# Sheet1.net
KiCad netlist of a schematic drawn in Altium Designer
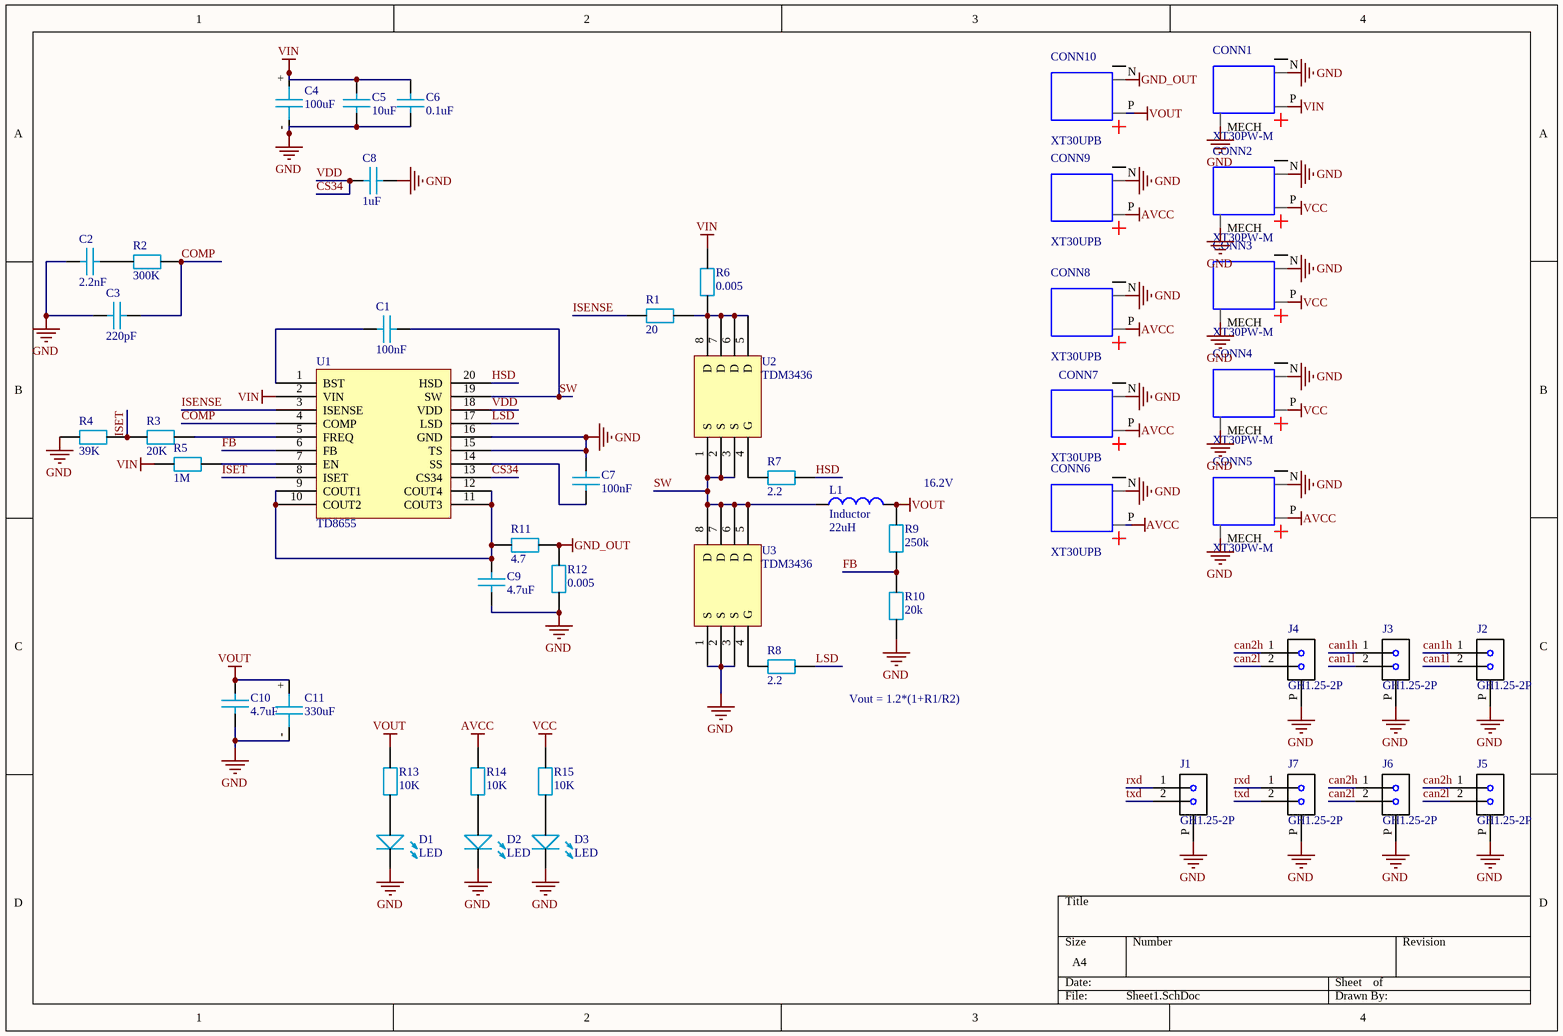
[diagram p0: Sheet1.SchDoc]

(export (version "E")
  (design (tool "Eeschema 10.0.6"))
  (components
    (comp (ref "C1") (value "100nF") (footprint "0603_C") (libsource (lib "elin私人订制") (part "C")))
    (comp (ref "C2") (value "2.2nF") (footprint "0603_C") (libsource (lib "elin私人订制") (part "C")))
    (comp (ref "C3") (value "220pF") (footprint "0603_C") (libsource (lib "elin私人订制") (part "C")))
    (comp (ref "C4") (value "100uF") (footprint "rad8*11") (libsource (lib "elin私人订制") (part "CD")))
    (comp (ref "C5") (value "10uF") (footprint "0805_C") (libsource (lib "elin私人订制") (part "C")))
    (comp (ref "C6") (value "0.1uF") (footprint "0805_C") (libsource (lib "elin私人订制") (part "C")))
    (comp (ref "C7") (value "100nF") (footprint "0603_C") (libsource (lib "elin私人订制") (part "C")))
    (comp (ref "C8") (value "1uF") (footprint "0603_C") (libsource (lib "elin私人订制") (part "C")))
    (comp (ref "C9") (value "4.7uF") (footprint "0603_C") (libsource (lib "elin私人订制") (part "C")))
    (comp (ref "C10") (value "4.7uF") (footprint "0805_C") (libsource (lib "elin私人订制") (part "C")))
    (comp (ref "C11") (value "330uF") (footprint "dip-ec10*17") (libsource (lib "elin私人订制") (part "CD")))
    (comp (ref "CONN1")
      (value "XT30PW-M")
      (footprint "xt30pw-m")
      (description "卧式焊板XT30（公）")
      (libsource (lib "RM私人定制") (part "XT30PW-M"))
    )
    (comp (ref "CONN2")
      (value "XT30PW-M")
      (footprint "xt30pw-m")
      (description "卧式焊板XT30（公）")
      (libsource (lib "RM私人定制") (part "XT30PW-M"))
    )
    (comp (ref "CONN3")
      (value "XT30PW-M")
      (footprint "xt30pw-m")
      (description "卧式焊板XT30（公）")
      (libsource (lib "RM私人定制") (part "XT30PW-M"))
    )
    (comp (ref "CONN4")
      (value "XT30PW-M")
      (footprint "xt30pw-m")
      (description "卧式焊板XT30（公）")
      (libsource (lib "RM私人定制") (part "XT30PW-M"))
    )
    (comp (ref "CONN5")
      (value "XT30PW-M")
      (footprint "xt30pw-m")
      (description "卧式焊板XT30（公）")
      (libsource (lib "RM私人定制") (part "XT30PW-M"))
    )
    (comp (ref "CONN6")
      (value "XT30UPB")
      (footprint "XT30UPB")
      (description "立式焊板XT30（通用）")
      (libsource (lib "RM私人定制") (part "XT30UPB"))
    )
    (comp (ref "CONN7")
      (value "XT30UPB")
      (footprint "XT30UPB")
      (description "立式焊板XT30（通用）")
      (libsource (lib "RM私人定制") (part "XT30UPB"))
    )
    (comp (ref "CONN8")
      (value "XT30UPB")
      (footprint "XT30UPB")
      (description "立式焊板XT30（通用）")
      (libsource (lib "RM私人定制") (part "XT30UPB"))
    )
    (comp (ref "CONN9")
      (value "XT30UPB")
      (footprint "XT30UPB")
      (description "立式焊板XT30（通用）")
      (libsource (lib "RM私人定制") (part "XT30UPB"))
    )
    (comp (ref "CONN10")
      (value "XT30UPB")
      (footprint "XT30UPB")
      (description "立式焊板XT30（通用）")
      (libsource (lib "RM私人定制") (part "XT30UPB"))
    )
    (comp (ref "D1") (value "LED") (footprint "LED_0805") (libsource (lib "elin私人订制") (part "LED")))
    (comp (ref "D2") (value "LED") (footprint "LED_0805") (libsource (lib "elin私人订制") (part "LED")))
    (comp (ref "D3") (value "LED") (footprint "LED_0805") (libsource (lib "elin私人订制") (part "LED")))
    (comp (ref "J1")
      (value "GH1.25-2P")
      (footprint "gh1.25-2p-立")
      (fields (field (name "MP") "53261-0271") (field (name "MF") "Molex"))
      (libsource (lib "RM私人定制") (part "GH1.25-2P"))
    )
    (comp (ref "J2")
      (value "GH1.25-2P")
      (footprint "gh1.25-2p-立")
      (fields (field (name "MP") "53261-0271") (field (name "MF") "Molex"))
      (libsource (lib "RM私人定制") (part "GH1.25-2P"))
    )
    (comp (ref "J3")
      (value "GH1.25-2P")
      (footprint "gh1.25-2p-立")
      (fields (field (name "MP") "53261-0271") (field (name "MF") "Molex"))
      (libsource (lib "RM私人定制") (part "GH1.25-2P"))
    )
    (comp (ref "J4")
      (value "GH1.25-2P")
      (footprint "gh1.25-2p-立")
      (fields (field (name "MP") "53261-0271") (field (name "MF") "Molex"))
      (libsource (lib "RM私人定制") (part "GH1.25-2P"))
    )
    (comp (ref "J5")
      (value "GH1.25-2P")
      (footprint "gh1.25-2p-立")
      (fields (field (name "MP") "53261-0271") (field (name "MF") "Molex"))
      (libsource (lib "RM私人定制") (part "GH1.25-2P"))
    )
    (comp (ref "J6")
      (value "GH1.25-2P")
      (footprint "gh1.25-2p-立")
      (fields (field (name "MP") "53261-0271") (field (name "MF") "Molex"))
      (libsource (lib "RM私人定制") (part "GH1.25-2P"))
    )
    (comp (ref "J7")
      (value "GH1.25-2P")
      (footprint "gh1.25-2p-立")
      (fields (field (name "MP") "53261-0271") (field (name "MF") "Molex"))
      (libsource (lib "RM私人定制") (part "GH1.25-2P"))
    )
    (comp (ref "L1")
      (value "Inductor")
      (footprint "SRP1265A-220M")
      (fields (field (name "ALTIUM_VALUE") "22uH") (field (name "PUBLISHER") "Altium Limited"))
      (libsource (lib "Miscellaneous Devices") (part "Inductor"))
    )
    (comp (ref "R1") (value "20") (footprint "0603-R") (libsource (lib "elin私人订制") (part "R")))
    (comp (ref "R2") (value "300K") (footprint "0603-R") (libsource (lib "elin私人订制") (part "R")))
    (comp (ref "R3") (value "20K") (footprint "0603-R") (libsource (lib "elin私人订制") (part "R")))
    (comp (ref "R4") (value "39K") (footprint "0603-R") (libsource (lib "elin私人订制") (part "R")))
    (comp (ref "R5") (value "1M") (footprint "0603-R") (libsource (lib "elin私人订制") (part "R")))
    (comp (ref "R6") (value "0.005") (footprint "2512") (libsource (lib "elin私人订制") (part "R")))
    (comp (ref "R7") (value "2.2") (footprint "0603-R") (libsource (lib "elin私人订制") (part "R")))
    (comp (ref "R8") (value "2.2") (footprint "0603-R") (libsource (lib "elin私人订制") (part "R")))
    (comp (ref "R9") (value "250k") (footprint "0603-R") (libsource (lib "elin私人订制") (part "R")))
    (comp (ref "R10") (value "20k") (footprint "0603-R") (libsource (lib "elin私人订制") (part "R")))
    (comp (ref "R11") (value "4.7") (footprint "0603-R") (libsource (lib "elin私人订制") (part "R")))
    (comp (ref "R12") (value "0.005") (footprint "2512") (libsource (lib "elin私人订制") (part "R")))
    (comp (ref "R13") (value "10K") (footprint "0603-R") (libsource (lib "elin私人订制") (part "R")))
    (comp (ref "R14") (value "10K") (footprint "0603-R") (libsource (lib "elin私人订制") (part "R")))
    (comp (ref "R15") (value "10K") (footprint "0603-R") (libsource (lib "elin私人订制") (part "R")))
    (comp (ref "U1")
      (value "TD8655")
      (footprint "LC-QFN-20_4x4x05P")
      (libsource (lib "elin私人订制") (part "TD8655"))
    )
    (comp (ref "U2")
      (value "TDM3436")
      (footprint "LC-DFN-8_5x6mm")
      (libsource (lib "elin私人订制") (part "TDM3436"))
    )
    (comp (ref "U3")
      (value "TDM3436")
      (footprint "LC-DFN-8_5x6mm")
      (libsource (lib "elin私人订制") (part "TDM3436"))
    )
  )
  (nets
    (net (code "1") (name "/COMP") (class "Default")
      (node (ref "C3") (pin "2") (pinfunction "2_2") (pintype "passive"))
      (node (ref "R2") (pin "2") (pinfunction "2_2") (pintype "passive"))
      (node (ref "U1") (pin "4") (pinfunction "COMP_4") (pintype "passive"))
    )
    (net (code "2") (name "/CS34") (class "Default")
      (node (ref "C8") (pin "2") (pinfunction "2_2") (pintype "passive"))
      (node (ref "U1") (pin "13") (pinfunction "CS34_13") (pintype "passive"))
      (node (ref "U1") (pin "18") (pinfunction "VDD_18") (pintype "passive"))
    )
    (net (code "3") (name "/FB") (class "Default")
      (node (ref "R10") (pin "2") (pinfunction "2_2") (pintype "passive"))
      (node (ref "R9") (pin "1") (pinfunction "1_1") (pintype "passive"))
      (node (ref "U1") (pin "6") (pinfunction "FB_6") (pintype "passive"))
    )
    (net (code "4") (name "/HSD") (class "Default")
      (node (ref "R7") (pin "1") (pinfunction "1_1") (pintype "passive"))
      (node (ref "U1") (pin "20") (pinfunction "HSD_20") (pintype "passive"))
    )
    (net (code "5") (name "/ISENSE") (class "Default")
      (node (ref "R1") (pin "1") (pinfunction "1_1") (pintype "passive"))
      (node (ref "U1") (pin "3") (pinfunction "ISENSE_3") (pintype "passive"))
    )
    (net (code "6") (name "/ISET") (class "Default")
      (node (ref "R3") (pin "1") (pinfunction "1_1") (pintype "passive"))
      (node (ref "R4") (pin "2") (pinfunction "2_2") (pintype "passive"))
      (node (ref "U1") (pin "8") (pinfunction "ISET_8") (pintype "passive"))
    )
    (net (code "7") (name "/LSD") (class "Default")
      (node (ref "R8") (pin "1") (pinfunction "1_1") (pintype "passive"))
      (node (ref "U1") (pin "17") (pinfunction "LSD_17") (pintype "passive"))
    )
    (net (code "8") (name "/SW") (class "Default")
      (node (ref "C1") (pin "1") (pinfunction "1_1") (pintype "passive"))
      (node (ref "L1") (pin "1") (pinfunction "1_1") (pintype "passive"))
      (node (ref "U1") (pin "19") (pinfunction "SW_19") (pintype "passive"))
      (node (ref "U2") (pin "1") (pinfunction "S_1") (pintype "passive"))
      (node (ref "U2") (pin "2") (pinfunction "S_2") (pintype "passive"))
      (node (ref "U2") (pin "3") (pinfunction "S_3") (pintype "passive"))
      (node (ref "U3") (pin "5") (pinfunction "D_5") (pintype "passive"))
      (node (ref "U3") (pin "6") (pinfunction "D_6") (pintype "passive"))
      (node (ref "U3") (pin "7") (pinfunction "D_7") (pintype "passive"))
      (node (ref "U3") (pin "8") (pinfunction "D_8") (pintype "passive"))
    )
    (net (code "9") (name "/can1h") (class "Default")
      (node (ref "J2") (pin "1") (pinfunction "1_1") (pintype "passive"))
      (node (ref "J3") (pin "1") (pinfunction "1_1") (pintype "passive"))
    )
    (net (code "10") (name "/can1l") (class "Default")
      (node (ref "J2") (pin "2") (pinfunction "2_2") (pintype "passive"))
      (node (ref "J3") (pin "2") (pinfunction "2_2") (pintype "passive"))
    )
    (net (code "11") (name "/can2h") (class "Default")
      (node (ref "J4") (pin "1") (pinfunction "1_1") (pintype "passive"))
      (node (ref "J5") (pin "1") (pinfunction "1_1") (pintype "passive"))
      (node (ref "J6") (pin "1") (pinfunction "1_1") (pintype "passive"))
    )
    (net (code "12") (name "/can2l") (class "Default")
      (node (ref "J4") (pin "2") (pinfunction "2_2") (pintype "passive"))
      (node (ref "J5") (pin "2") (pinfunction "2_2") (pintype "passive"))
      (node (ref "J6") (pin "2") (pinfunction "2_2") (pintype "passive"))
    )
    (net (code "13") (name "/rxd") (class "Default")
      (node (ref "J1") (pin "1") (pinfunction "1_1") (pintype "passive"))
      (node (ref "J7") (pin "1") (pinfunction "1_1") (pintype "passive"))
    )
    (net (code "14") (name "/txd") (class "Default")
      (node (ref "J1") (pin "2") (pinfunction "2_2") (pintype "passive"))
      (node (ref "J7") (pin "2") (pinfunction "2_2") (pintype "passive"))
    )
    (net (code "15") (name "AVCC") (class "Default")
      (node (ref "CONN5") (pin "P") (pintype "passive"))
      (node (ref "CONN6") (pin "P") (pintype "passive"))
      (node (ref "CONN7") (pin "P") (pintype "passive"))
      (node (ref "CONN8") (pin "P") (pintype "passive"))
      (node (ref "CONN9") (pin "P") (pintype "passive"))
      (node (ref "R14") (pin "2") (pinfunction "2_2") (pintype "passive"))
    )
    (net (code "16") (name "GND") (class "Default")
      (node (ref "C10") (pin "1") (pinfunction "1_1") (pintype "passive"))
      (node (ref "C11") (pin "-") (pinfunction "2_-") (pintype "passive"))
      (node (ref "C2") (pin "1") (pinfunction "1_1") (pintype "passive"))
      (node (ref "C3") (pin "1") (pinfunction "1_1") (pintype "passive"))
      (node (ref "C4") (pin "-") (pinfunction "2_-") (pintype "passive"))
      (node (ref "C5") (pin "1") (pinfunction "1_1") (pintype "passive"))
      (node (ref "C6") (pin "1") (pinfunction "1_1") (pintype "passive"))
      (node (ref "C7") (pin "2") (pinfunction "2_2") (pintype "passive"))
      (node (ref "C8") (pin "1") (pinfunction "1_1") (pintype "passive"))
      (node (ref "C9") (pin "1") (pinfunction "1_1") (pintype "passive"))
      (node (ref "CONN1") (pin "3") (pinfunction "MECH_3") (pintype "passive"))
      (node (ref "CONN1") (pin "N") (pintype "passive"))
      (node (ref "CONN2") (pin "3") (pinfunction "MECH_3") (pintype "passive"))
      (node (ref "CONN2") (pin "N") (pintype "passive"))
      (node (ref "CONN3") (pin "3") (pinfunction "MECH_3") (pintype "passive"))
      (node (ref "CONN3") (pin "N") (pintype "passive"))
      (node (ref "CONN4") (pin "3") (pinfunction "MECH_3") (pintype "passive"))
      (node (ref "CONN4") (pin "N") (pintype "passive"))
      (node (ref "CONN5") (pin "3") (pinfunction "MECH_3") (pintype "passive"))
      (node (ref "CONN5") (pin "N") (pintype "passive"))
      (node (ref "CONN6") (pin "N") (pintype "passive"))
      (node (ref "CONN7") (pin "N") (pintype "passive"))
      (node (ref "CONN8") (pin "N") (pintype "passive"))
      (node (ref "CONN9") (pin "N") (pintype "passive"))
      (node (ref "D1") (pin "2") (pinfunction "2_2") (pintype "passive"))
      (node (ref "D2") (pin "2") (pinfunction "2_2") (pintype "passive"))
      (node (ref "D3") (pin "2") (pinfunction "2_2") (pintype "passive"))
      (node (ref "J1") (pin "P") (pinfunction "3_P") (pintype "passive"))
      (node (ref "J2") (pin "P") (pinfunction "3_P") (pintype "passive"))
      (node (ref "J3") (pin "P") (pinfunction "3_P") (pintype "passive"))
      (node (ref "J4") (pin "P") (pinfunction "3_P") (pintype "passive"))
      (node (ref "J5") (pin "P") (pinfunction "3_P") (pintype "passive"))
      (node (ref "J6") (pin "P") (pinfunction "3_P") (pintype "passive"))
      (node (ref "J7") (pin "P") (pinfunction "3_P") (pintype "passive"))
      (node (ref "R10") (pin "1") (pinfunction "1_1") (pintype "passive"))
      (node (ref "R12") (pin "1") (pinfunction "1_1") (pintype "passive"))
      (node (ref "R4") (pin "1") (pinfunction "1_1") (pintype "passive"))
      (node (ref "U1") (pin "15") (pinfunction "TS_15") (pintype "passive"))
      (node (ref "U1") (pin "16") (pinfunction "GND_16") (pintype "passive"))
      (node (ref "U3") (pin "1") (pinfunction "S_1") (pintype "passive"))
      (node (ref "U3") (pin "2") (pinfunction "S_2") (pintype "passive"))
      (node (ref "U3") (pin "3") (pinfunction "S_3") (pintype "passive"))
    )
    (net (code "17") (name "GND_OUT") (class "Default")
      (node (ref "CONN10") (pin "N") (pintype "passive"))
      (node (ref "R11") (pin "2") (pinfunction "2_2") (pintype "passive"))
      (node (ref "R12") (pin "2") (pinfunction "2_2") (pintype "passive"))
    )
    (net (code "18") (name "Net-(C2-Pad2)") (class "Default")
      (node (ref "C2") (pin "2") (pinfunction "2_2") (pintype "passive"))
      (node (ref "R2") (pin "1") (pinfunction "1_1") (pintype "passive"))
    )
    (net (code "19") (name "Net-(D1-Pad1)") (class "Default")
      (node (ref "D1") (pin "1") (pinfunction "1_1") (pintype "passive"))
      (node (ref "R13") (pin "1") (pinfunction "1_1") (pintype "passive"))
    )
    (net (code "20") (name "Net-(D2-Pad1)") (class "Default")
      (node (ref "D2") (pin "1") (pinfunction "1_1") (pintype "passive"))
      (node (ref "R14") (pin "1") (pinfunction "1_1") (pintype "passive"))
    )
    (net (code "21") (name "Net-(D3-Pad1)") (class "Default")
      (node (ref "D3") (pin "1") (pinfunction "1_1") (pintype "passive"))
      (node (ref "R15") (pin "1") (pinfunction "1_1") (pintype "passive"))
    )
    (net (code "22") (name "Net-(R1-Pad2)") (class "Default")
      (node (ref "R1") (pin "2") (pinfunction "2_2") (pintype "passive"))
      (node (ref "R6") (pin "1") (pinfunction "1_1") (pintype "passive"))
      (node (ref "U2") (pin "5") (pinfunction "D_5") (pintype "passive"))
      (node (ref "U2") (pin "6") (pinfunction "D_6") (pintype "passive"))
      (node (ref "U2") (pin "7") (pinfunction "D_7") (pintype "passive"))
      (node (ref "U2") (pin "8") (pinfunction "D_8") (pintype "passive"))
    )
    (net (code "23") (name "Net-(U1-BST)") (class "Default")
      (node (ref "C1") (pin "2") (pinfunction "2_2") (pintype "passive"))
      (node (ref "U1") (pin "1") (pinfunction "BST_1") (pintype "passive"))
    )
    (net (code "24") (name "Net-(U1-COUT1)") (class "Default")
      (node (ref "C9") (pin "2") (pinfunction "2_2") (pintype "passive"))
      (node (ref "R11") (pin "1") (pinfunction "1_1") (pintype "passive"))
      (node (ref "U1") (pin "10") (pinfunction "COUT2_10") (pintype "passive"))
      (node (ref "U1") (pin "11") (pinfunction "COUT3_11") (pintype "passive"))
      (node (ref "U1") (pin "12") (pinfunction "COUT4_12") (pintype "passive"))
      (node (ref "U1") (pin "9") (pinfunction "COUT1_9") (pintype "passive"))
    )
    (net (code "25") (name "Net-(U1-EN)") (class "Default")
      (node (ref "R5") (pin "2") (pinfunction "2_2") (pintype "passive"))
      (node (ref "U1") (pin "7") (pinfunction "EN_7") (pintype "passive"))
    )
    (net (code "26") (name "Net-(U1-FREQ)") (class "Default")
      (node (ref "R3") (pin "2") (pinfunction "2_2") (pintype "passive"))
      (node (ref "U1") (pin "5") (pinfunction "FREQ_5") (pintype "passive"))
    )
    (net (code "27") (name "Net-(U1-SS)") (class "Default")
      (node (ref "C7") (pin "1") (pinfunction "1_1") (pintype "passive"))
      (node (ref "U1") (pin "14") (pinfunction "SS_14") (pintype "passive"))
    )
    (net (code "28") (name "Net-(U2-G)") (class "Default")
      (node (ref "R7") (pin "2") (pinfunction "2_2") (pintype "passive"))
      (node (ref "U2") (pin "4") (pinfunction "G_4") (pintype "passive"))
    )
    (net (code "29") (name "Net-(U3-G)") (class "Default")
      (node (ref "R8") (pin "2") (pinfunction "2_2") (pintype "passive"))
      (node (ref "U3") (pin "4") (pinfunction "G_4") (pintype "passive"))
    )
    (net (code "30") (name "VCC") (class "Default")
      (node (ref "CONN2") (pin "P") (pintype "passive"))
      (node (ref "CONN3") (pin "P") (pintype "passive"))
      (node (ref "CONN4") (pin "P") (pintype "passive"))
      (node (ref "R15") (pin "2") (pinfunction "2_2") (pintype "passive"))
    )
    (net (code "31") (name "VIN") (class "Default")
      (node (ref "C4") (pin "+") (pinfunction "1_+") (pintype "passive"))
      (node (ref "C5") (pin "2") (pinfunction "2_2") (pintype "passive"))
      (node (ref "C6") (pin "2") (pinfunction "2_2") (pintype "passive"))
      (node (ref "CONN1") (pin "P") (pintype "passive"))
      (node (ref "R5") (pin "1") (pinfunction "1_1") (pintype "passive"))
      (node (ref "R6") (pin "2") (pinfunction "2_2") (pintype "passive"))
      (node (ref "U1") (pin "2") (pinfunction "VIN_2") (pintype "passive"))
    )
    (net (code "32") (name "VOUT") (class "Default")
      (node (ref "C10") (pin "2") (pinfunction "2_2") (pintype "passive"))
      (node (ref "C11") (pin "+") (pinfunction "1_+") (pintype "passive"))
      (node (ref "CONN10") (pin "P") (pintype "passive"))
      (node (ref "L1") (pin "2") (pinfunction "2_2") (pintype "passive"))
      (node (ref "R13") (pin "2") (pinfunction "2_2") (pintype "passive"))
      (node (ref "R9") (pin "2") (pinfunction "2_2") (pintype "passive"))
    )
  )
)
